# SCH.net
KiCad netlist of a schematic drawn in Altium Designer
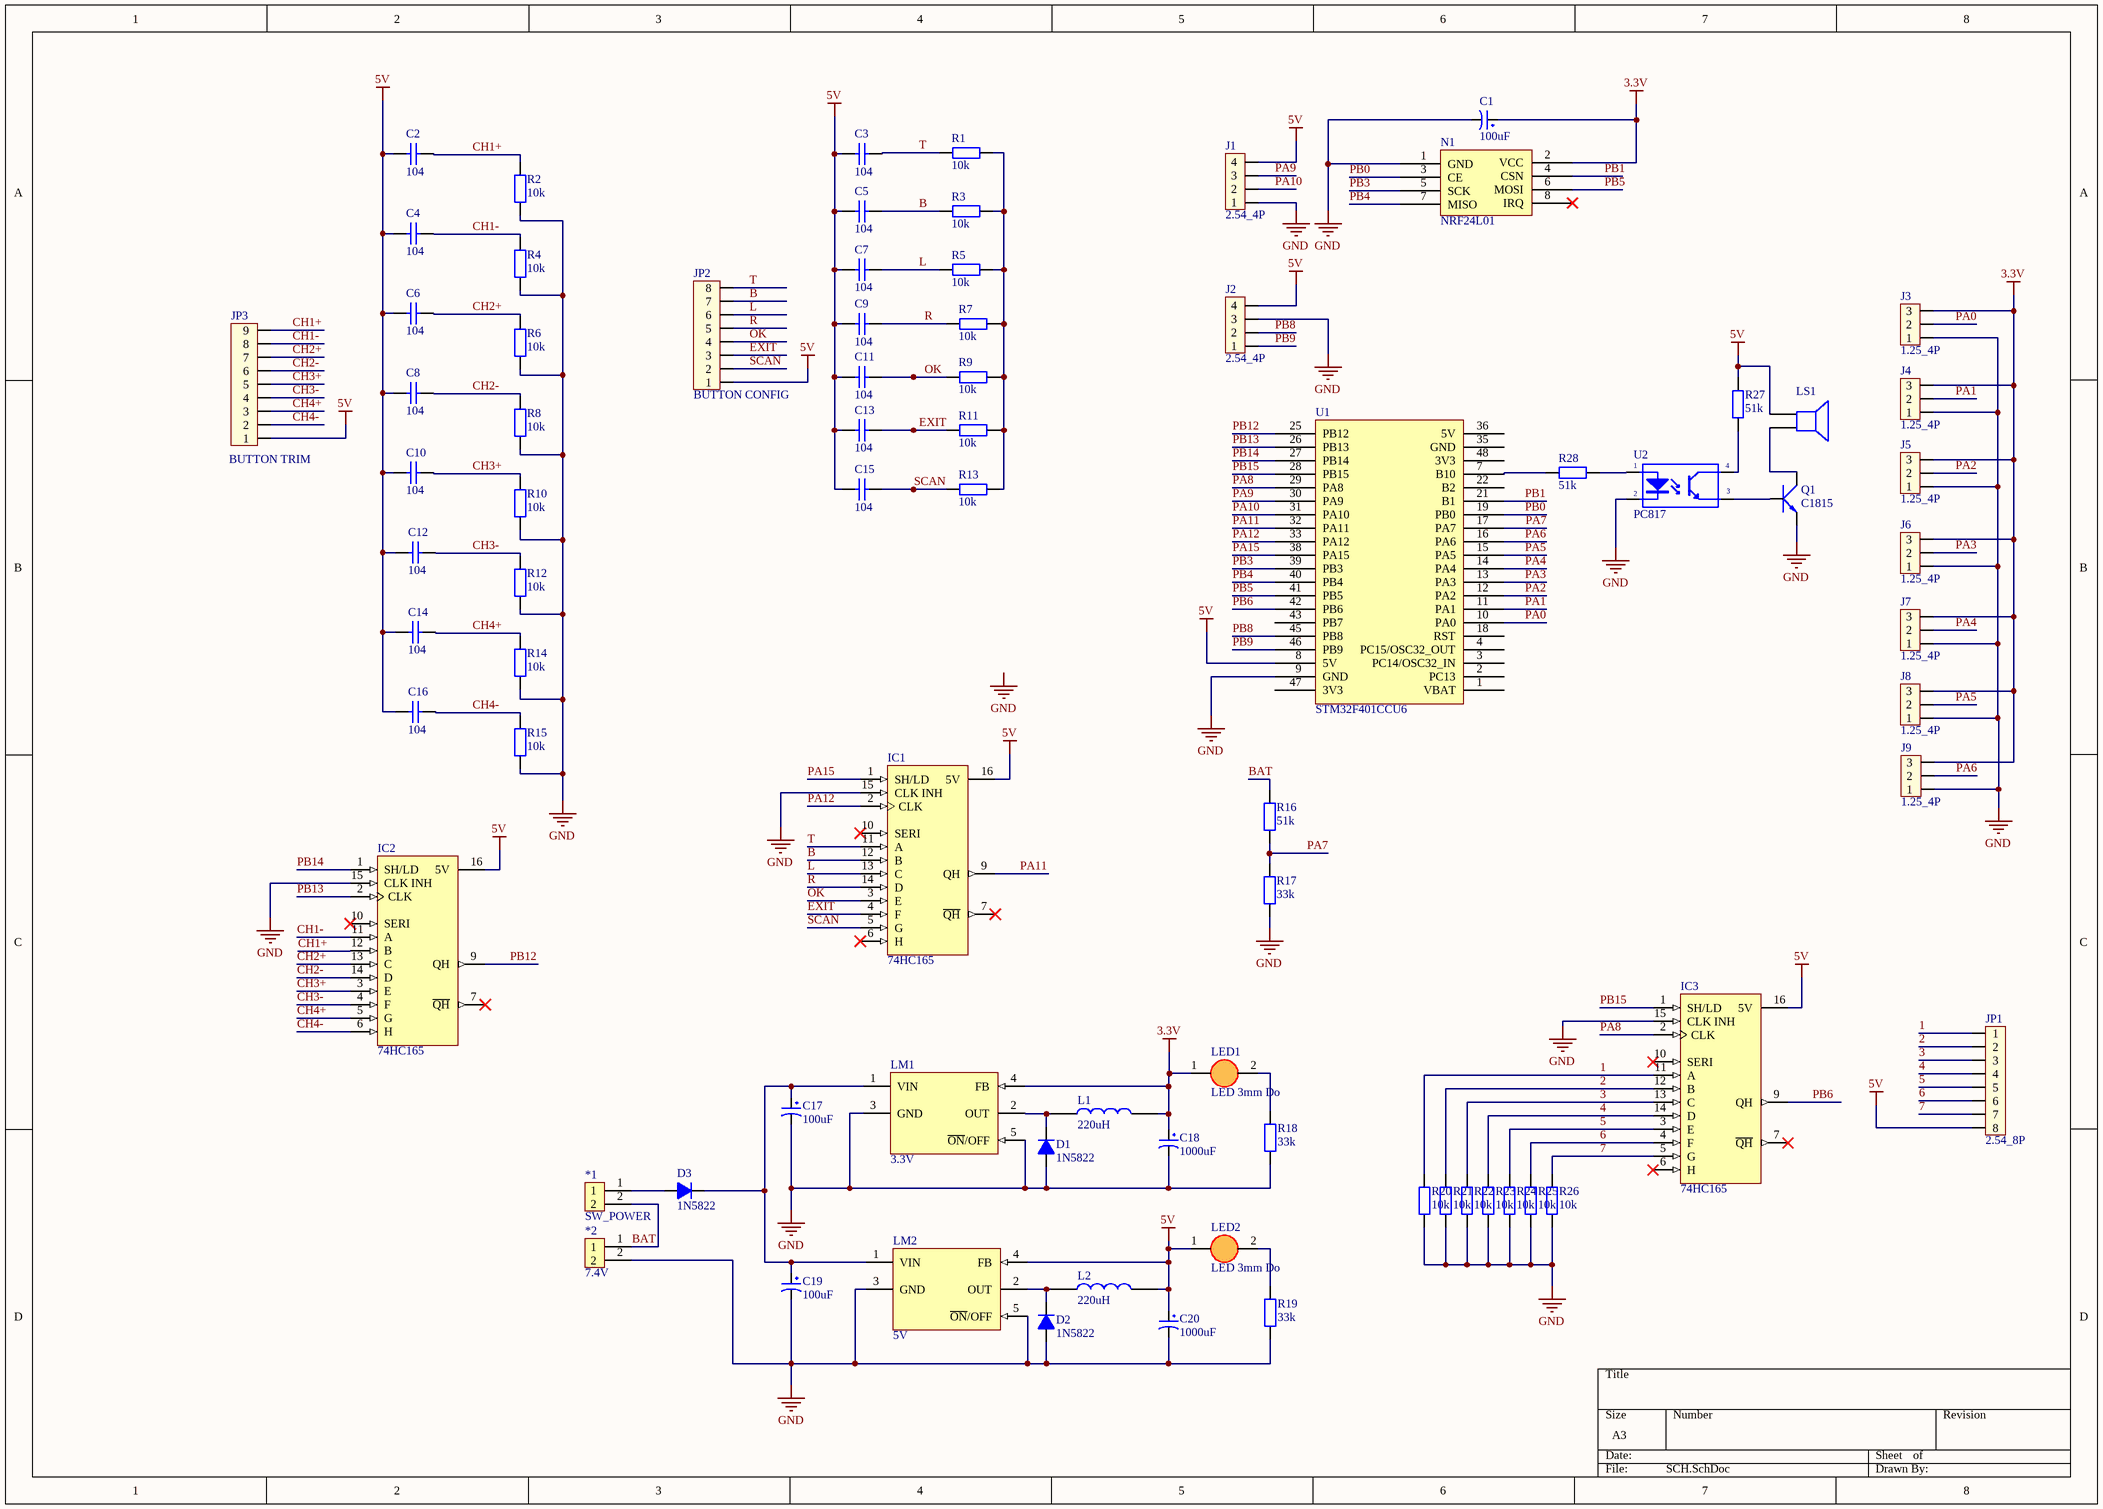
[diagram p0: SCH.SchDoc]

(export (version "E")
  (design (tool "Eeschema 10.0.6"))
  (components
    (comp (ref "*1")
      (value "SW_POWER")
      (footprint "jump don duc_2p")
      (libsource (lib "THU VIEN SCH") (part "jump don duc 2.54_2p"))
    )
    (comp (ref "*2")
      (value "7.4V")
      (footprint "jump don duc_2p")
      (libsource (lib "THU VIEN SCH") (part "jump don duc 2.54_2p"))
    )
    (comp (ref "C1")
      (value "100uF")
      (footprint "tu hoa 5mm")
      (description "Cắm")
      (libsource (lib "THU VIEN SCH") (part "Tu Hoa 100uF 25V 6x11"))
    )
    (comp (ref "C2")
      (value "104")
      (footprint "tu gom")
      (description "Cắm")
      (libsource (lib "THU VIEN SCH") (part "Tu gom 104 50V"))
    )
    (comp (ref "C3")
      (value "104")
      (footprint "tu gom")
      (description "Cắm")
      (libsource (lib "THU VIEN SCH") (part "Tu gom 104 50V"))
    )
    (comp (ref "C4")
      (value "104")
      (footprint "tu gom")
      (description "Cắm")
      (libsource (lib "THU VIEN SCH") (part "Tu gom 104 50V"))
    )
    (comp (ref "C5")
      (value "104")
      (footprint "tu gom")
      (description "Cắm")
      (libsource (lib "THU VIEN SCH") (part "Tu gom 104 50V"))
    )
    (comp (ref "C6")
      (value "104")
      (footprint "tu gom")
      (description "Cắm")
      (libsource (lib "THU VIEN SCH") (part "Tu gom 104 50V"))
    )
    (comp (ref "C7")
      (value "104")
      (footprint "tu gom")
      (description "Cắm")
      (libsource (lib "THU VIEN SCH") (part "Tu gom 104 50V"))
    )
    (comp (ref "C8")
      (value "104")
      (footprint "tu gom")
      (description "Cắm")
      (libsource (lib "THU VIEN SCH") (part "Tu gom 104 50V"))
    )
    (comp (ref "C9")
      (value "104")
      (footprint "tu gom")
      (description "Cắm")
      (libsource (lib "THU VIEN SCH") (part "Tu gom 104 50V"))
    )
    (comp (ref "C10")
      (value "104")
      (footprint "tu gom")
      (description "Cắm")
      (libsource (lib "THU VIEN SCH") (part "Tu gom 104 50V"))
    )
    (comp (ref "C11")
      (value "104")
      (footprint "tu gom")
      (description "Cắm")
      (libsource (lib "THU VIEN SCH") (part "Tu gom 104 50V"))
    )
    (comp (ref "C12")
      (value "104")
      (footprint "tu gom")
      (description "Cắm")
      (libsource (lib "THU VIEN SCH") (part "Tu gom 104 50V"))
    )
    (comp (ref "C13")
      (value "104")
      (footprint "tu gom")
      (description "Cắm")
      (libsource (lib "THU VIEN SCH") (part "Tu gom 104 50V"))
    )
    (comp (ref "C14")
      (value "104")
      (footprint "tu gom")
      (description "Cắm")
      (libsource (lib "THU VIEN SCH") (part "Tu gom 104 50V"))
    )
    (comp (ref "C15")
      (value "104")
      (footprint "tu gom")
      (description "Cắm")
      (libsource (lib "THU VIEN SCH") (part "Tu gom 104 50V"))
    )
    (comp (ref "C16")
      (value "104")
      (footprint "tu gom")
      (description "Cắm")
      (libsource (lib "THU VIEN SCH") (part "Tu gom 104 50V"))
    )
    (comp (ref "C17")
      (value "100uF")
      (footprint "tu hoa 8mm")
      (description "Cắm")
      (libsource (lib "THU VIEN SCH") (part "Tu Hoa 100uF 50V 8x11"))
    )
    (comp (ref "C18")
      (value "1000uF")
      (footprint "tu hoa 8mm")
      (description "Cắm")
      (libsource (lib "THU VIEN SCH") (part "Tu Hoa 1000uF 16V 8x20"))
    )
    (comp (ref "C19")
      (value "100uF")
      (footprint "tu hoa 8mm")
      (description "Cắm")
      (libsource (lib "THU VIEN SCH") (part "Tu Hoa 100uF 50V 8x11"))
    )
    (comp (ref "C20")
      (value "1000uF")
      (footprint "tu hoa 8mm")
      (description "Cắm")
      (libsource (lib "THU VIEN SCH") (part "Tu Hoa 1000uF 16V 8x20"))
    )
    (comp (ref "D1")
      (value "1N5822")
      (footprint "D5A")
      (description "Diode 5A")
      (libsource (lib "syhaunguyen") (part "D5A"))
    )
    (comp (ref "D2")
      (value "1N5822")
      (footprint "D5A")
      (description "Diode 5A")
      (libsource (lib "syhaunguyen") (part "D5A"))
    )
    (comp (ref "D3")
      (value "1N5822")
      (footprint "D5A")
      (description "Diode 5A")
      (libsource (lib "syhaunguyen") (part "D5A"))
    )
    (comp (ref "IC1")
      (value "74HC165")
      (footprint "DIP16/W0.3")
      (description "8-Bit Parallel In/Serial Out Shift Register")
      (libsource (lib "syhaunguyen") (part "74HC165"))
    )
    (comp (ref "IC2")
      (value "74HC165")
      (footprint "DIP16/W0.3")
      (description "8-Bit Parallel In/Serial Out Shift Register")
      (libsource (lib "syhaunguyen") (part "74HC165"))
    )
    (comp (ref "IC3")
      (value "74HC165")
      (footprint "DIP16/W0.3")
      (description "8-Bit Parallel In/Serial Out Shift Register")
      (libsource (lib "syhaunguyen") (part "74HC165"))
    )
    (comp (ref "J1")
      (value "2.54_4P")
      (footprint "JP4")
      (description "Cắm")
      (libsource (lib "THU VIEN SCH") (part "Jum Don Duc 2.54_4P"))
    )
    (comp (ref "J2")
      (value "2.54_4P")
      (footprint "JP4")
      (description "Cắm")
      (libsource (lib "THU VIEN SCH") (part "Jum Don Duc 2.54_4P"))
    )
    (comp (ref "J3")
      (value "1.25_4P")
      (footprint "ZH1.25 3P")
      (description "Cắm")
      (libsource (lib "THU VIEN SCH") (part "ZH1.25 3P"))
    )
    (comp (ref "J4")
      (value "1.25_4P")
      (footprint "ZH1.25 3P")
      (description "Cắm")
      (libsource (lib "THU VIEN SCH") (part "ZH1.25 3P"))
    )
    (comp (ref "J5")
      (value "1.25_4P")
      (footprint "ZH1.25 3P")
      (description "Cắm")
      (libsource (lib "THU VIEN SCH") (part "ZH1.25 3P"))
    )
    (comp (ref "J6")
      (value "1.25_4P")
      (footprint "ZH1.25 3P")
      (description "Cắm")
      (libsource (lib "THU VIEN SCH") (part "ZH1.25 3P"))
    )
    (comp (ref "J7")
      (value "1.25_4P")
      (footprint "ZH1.25 3P")
      (description "Cắm")
      (libsource (lib "THU VIEN SCH") (part "ZH1.25 3P"))
    )
    (comp (ref "J8")
      (value "1.25_4P")
      (footprint "ZH1.25 3P")
      (description "Cắm")
      (libsource (lib "THU VIEN SCH") (part "ZH1.25 3P"))
    )
    (comp (ref "J9")
      (value "1.25_4P")
      (footprint "ZH1.25 3P")
      (description "Cắm")
      (libsource (lib "THU VIEN SCH") (part "ZH1.25 3P"))
    )
    (comp (ref "JP1")
      (value "2.54_8P")
      (footprint "JP8")
      (description "Cắm")
      (libsource (lib "THU VIEN SCH") (part "Jum Don Duc 2.54_8P"))
    )
    (comp (ref "JP2")
      (value "BUTTON CONFIG")
      (footprint "CON8")
      (description "Cắm")
      (libsource (lib "THU VIEN SCH") (part "Con_8"))
    )
    (comp (ref "JP3")
      (value "BUTTON TRIM")
      (footprint "CON9")
      (description "Cắm")
      (libsource (lib "THU VIEN SCH") (part "Con_9"))
    )
    (comp (ref "L1")
      (value "220uH")
      (footprint "CUON CAM 100uH3A")
      (description "Cắm")
      (libsource (lib "THU VIEN SCH") (part "CUON CAM 470uH DIP"))
    )
    (comp (ref "L2")
      (value "220uH")
      (footprint "CUON CAM 100uH3A")
      (description "Cắm")
      (libsource (lib "THU VIEN SCH") (part "CUON CAM 470uH DIP"))
    )
    (comp (ref "LED1")
      (value "LED 3mm Do")
      (footprint "LED 3mm Do")
      (description "Cắm")
      (libsource (lib "THU VIEN SCH") (part "LED 3mm Do"))
    )
    (comp (ref "LED2")
      (value "LED 3mm Do")
      (footprint "LED 3mm Do")
      (description "Cắm")
      (libsource (lib "THU VIEN SCH") (part "LED 3mm Do"))
    )
    (comp (ref "LM1")
      (value "3.3V")
      (footprint "LM2576-5V")
      (description "Cắm")
      (libsource (lib "THU VIEN SCH") (part "LM2576_3.3V."))
    )
    (comp (ref "LM2")
      (value "5V")
      (footprint "LM2576-5V")
      (description "Cắm")
      (libsource (lib "THU VIEN SCH") (part "LM2576_5V"))
    )
    (comp (ref "LS1")
      (value "~")
      (footprint "SPEAKER")
      (description "Cắm")
      (libsource (lib "THU VIEN SCH") (part "Coi Chip 5V"))
    )
    (comp (ref "N1")
      (value "NRF24L01")
      (footprint "NRF24L01")
      (libsource (lib "THU VIEN SCH") (part "NRF24L01"))
    )
    (comp (ref "Q1")
      (value "C1815")
      (footprint "QTO-92")
      (description "NPN 600mW, ECB")
      (libsource (lib "syhaunguyen") (part "C1815"))
    )
    (comp (ref "R1")
      (value "10k")
      (footprint "tro vach 1/4w")
      (description "Căm")
      (libsource (lib "THU VIEN SCH") (part "Tro Vach 1/4W 5% 10k"))
    )
    (comp (ref "R2")
      (value "10k")
      (footprint "tro vach 1/4w")
      (description "Căm")
      (libsource (lib "THU VIEN SCH") (part "Tro Vach 1/4W 5% 10k"))
    )
    (comp (ref "R3")
      (value "10k")
      (footprint "tro vach 1/4w")
      (description "Căm")
      (libsource (lib "THU VIEN SCH") (part "Tro Vach 1/4W 5% 10k"))
    )
    (comp (ref "R4")
      (value "10k")
      (footprint "tro vach 1/4w")
      (description "Căm")
      (libsource (lib "THU VIEN SCH") (part "Tro Vach 1/4W 5% 10k"))
    )
    (comp (ref "R5")
      (value "10k")
      (footprint "tro vach 1/4w")
      (description "Căm")
      (libsource (lib "THU VIEN SCH") (part "Tro Vach 1/4W 5% 10k"))
    )
    (comp (ref "R6")
      (value "10k")
      (footprint "tro vach 1/4w")
      (description "Căm")
      (libsource (lib "THU VIEN SCH") (part "Tro Vach 1/4W 5% 10k"))
    )
    (comp (ref "R7")
      (value "10k")
      (footprint "tro vach 1/4w")
      (description "Căm")
      (libsource (lib "THU VIEN SCH") (part "Tro Vach 1/4W 5% 10k"))
    )
    (comp (ref "R8")
      (value "10k")
      (footprint "tro vach 1/4w")
      (description "Căm")
      (libsource (lib "THU VIEN SCH") (part "Tro Vach 1/4W 5% 10k"))
    )
    (comp (ref "R9")
      (value "10k")
      (footprint "tro vach 1/4w")
      (description "Căm")
      (libsource (lib "THU VIEN SCH") (part "Tro Vach 1/4W 5% 10k"))
    )
    (comp (ref "R10")
      (value "10k")
      (footprint "tro vach 1/4w")
      (description "Căm")
      (libsource (lib "THU VIEN SCH") (part "Tro Vach 1/4W 5% 10k"))
    )
    (comp (ref "R11")
      (value "10k")
      (footprint "tro vach 1/4w")
      (description "Căm")
      (libsource (lib "THU VIEN SCH") (part "Tro Vach 1/4W 5% 10k"))
    )
    (comp (ref "R12")
      (value "10k")
      (footprint "tro vach 1/4w")
      (description "Căm")
      (libsource (lib "THU VIEN SCH") (part "Tro Vach 1/4W 5% 10k"))
    )
    (comp (ref "R13")
      (value "10k")
      (footprint "tro vach 1/4w")
      (description "Căm")
      (libsource (lib "THU VIEN SCH") (part "Tro Vach 1/4W 5% 10k"))
    )
    (comp (ref "R14")
      (value "10k")
      (footprint "tro vach 1/4w")
      (description "Căm")
      (libsource (lib "THU VIEN SCH") (part "Tro Vach 1/4W 5% 10k"))
    )
    (comp (ref "R15")
      (value "10k")
      (footprint "tro vach 1/4w")
      (description "Căm")
      (libsource (lib "THU VIEN SCH") (part "Tro Vach 1/4W 5% 10k"))
    )
    (comp (ref "R16")
      (value "51k")
      (footprint "tro vach 1/4w")
      (description "Căm")
      (libsource (lib "THU VIEN SCH") (part "Tro Vach 1/4W 5% 10k"))
    )
    (comp (ref "R17")
      (value "33k")
      (footprint "tro vach 1/4w")
      (description "Căm")
      (libsource (lib "THU VIEN SCH") (part "Tro Vach 1/4W 5% 10k"))
    )
    (comp (ref "R18")
      (value "33k")
      (footprint "tro vach 1/4w")
      (description "Căm")
      (libsource (lib "THU VIEN SCH") (part "Tro Vach 1/4W 5% 10k"))
    )
    (comp (ref "R19")
      (value "33k")
      (footprint "tro vach 1/4w")
      (description "Căm")
      (libsource (lib "THU VIEN SCH") (part "Tro Vach 1/4W 5% 10k"))
    )
    (comp (ref "R20")
      (value "10k")
      (footprint "tro vach 1/4w")
      (description "Căm")
      (libsource (lib "THU VIEN SCH") (part "Tro Vach 1/4W 5% 10k"))
    )
    (comp (ref "R21")
      (value "10k")
      (footprint "tro vach 1/4w")
      (description "Căm")
      (libsource (lib "THU VIEN SCH") (part "Tro Vach 1/4W 5% 10k"))
    )
    (comp (ref "R22")
      (value "10k")
      (footprint "tro vach 1/4w")
      (description "Căm")
      (libsource (lib "THU VIEN SCH") (part "Tro Vach 1/4W 5% 10k"))
    )
    (comp (ref "R23")
      (value "10k")
      (footprint "tro vach 1/4w")
      (description "Căm")
      (libsource (lib "THU VIEN SCH") (part "Tro Vach 1/4W 5% 10k"))
    )
    (comp (ref "R24")
      (value "10k")
      (footprint "tro vach 1/4w")
      (description "Căm")
      (libsource (lib "THU VIEN SCH") (part "Tro Vach 1/4W 5% 10k"))
    )
    (comp (ref "R25")
      (value "10k")
      (footprint "tro vach 1/4w")
      (description "Căm")
      (libsource (lib "THU VIEN SCH") (part "Tro Vach 1/4W 5% 10k"))
    )
    (comp (ref "R26")
      (value "10k")
      (footprint "tro vach 1/4w")
      (description "Căm")
      (libsource (lib "THU VIEN SCH") (part "Tro Vach 1/4W 5% 10k"))
    )
    (comp (ref "R27")
      (value "51k")
      (footprint "tro vach 1/4w")
      (description "Căm")
      (libsource (lib "THU VIEN SCH") (part "Tro Vach 1/4W 5% 10k"))
    )
    (comp (ref "R28")
      (value "51k")
      (footprint "tro vach 1/4w")
      (description "Căm")
      (libsource (lib "THU VIEN SCH") (part "Tro Vach 1/4W 5% 10k"))
    )
    (comp (ref "U1")
      (value "STM32F401CCU6")
      (footprint "STM32F401CCU6")
      (libsource (lib "THU VIEN SCH") (part "STM32F401CCU6"))
    )
    (comp (ref "U2")
      (value "PC817")
      (footprint "DIP4/W0.3")
      (description "Single Opto")
      (libsource (lib "syhaunguyen") (part "PC817"))
    )
  )
  (nets
    (net (code "1") (name "/1") (class "Default")
      (node (ref "IC3") (pin "11") (pinfunction "A_11") (pintype "input"))
      (node (ref "JP1") (pin "1") (pinfunction "1_1") (pintype "passive"))
      (node (ref "R20") (pin "2") (pinfunction "2_2") (pintype "passive"))
    )
    (net (code "2") (name "/2") (class "Default")
      (node (ref "IC3") (pin "12") (pinfunction "B_12") (pintype "input"))
      (node (ref "JP1") (pin "2") (pinfunction "2_2") (pintype "passive"))
      (node (ref "R21") (pin "2") (pinfunction "2_2") (pintype "passive"))
    )
    (net (code "3") (name "/3") (class "Default")
      (node (ref "IC3") (pin "13") (pinfunction "C_13") (pintype "input"))
      (node (ref "JP1") (pin "3") (pinfunction "3_3") (pintype "passive"))
      (node (ref "R22") (pin "2") (pinfunction "2_2") (pintype "passive"))
    )
    (net (code "4") (name "/4") (class "Default")
      (node (ref "IC3") (pin "14") (pinfunction "D_14") (pintype "input"))
      (node (ref "JP1") (pin "4") (pinfunction "4_4") (pintype "passive"))
      (node (ref "R23") (pin "2") (pinfunction "2_2") (pintype "passive"))
    )
    (net (code "5") (name "/5") (class "Default")
      (node (ref "IC3") (pin "3") (pinfunction "E_3") (pintype "input"))
      (node (ref "JP1") (pin "5") (pinfunction "5_5") (pintype "passive"))
      (node (ref "R24") (pin "2") (pinfunction "2_2") (pintype "passive"))
    )
    (net (code "6") (name "/6") (class "Default")
      (node (ref "IC3") (pin "4") (pinfunction "F_4") (pintype "input"))
      (node (ref "JP1") (pin "6") (pinfunction "6_6") (pintype "passive"))
      (node (ref "R25") (pin "2") (pinfunction "2_2") (pintype "passive"))
    )
    (net (code "7") (name "/7") (class "Default")
      (node (ref "IC3") (pin "5") (pinfunction "G_5") (pintype "input"))
      (node (ref "JP1") (pin "7") (pinfunction "7_7") (pintype "passive"))
      (node (ref "R26") (pin "2") (pinfunction "2_2") (pintype "passive"))
    )
    (net (code "8") (name "/B") (class "Default")
      (node (ref "C5") (pin "1") (pinfunction "1_1") (pintype "passive"))
      (node (ref "IC1") (pin "12") (pinfunction "B_12") (pintype "input"))
      (node (ref "JP2") (pin "7") (pinfunction "7_7") (pintype "passive"))
      (node (ref "R3") (pin "1") (pinfunction "1_1") (pintype "passive"))
    )
    (net (code "9") (name "/BAT") (class "Default")
      (node (ref "*1") (pin "2") (pinfunction "2_2") (pintype "passive"))
      (node (ref "*2") (pin "1") (pinfunction "1_1") (pintype "passive"))
      (node (ref "R16") (pin "2") (pinfunction "2_2") (pintype "passive"))
    )
    (net (code "10") (name "/CH1+") (class "Default")
      (node (ref "C2") (pin "1") (pinfunction "1_1") (pintype "passive"))
      (node (ref "IC2") (pin "12") (pinfunction "B_12") (pintype "input"))
      (node (ref "JP3") (pin "9") (pinfunction "9_9") (pintype "passive"))
      (node (ref "R2") (pin "1") (pinfunction "1_1") (pintype "passive"))
    )
    (net (code "11") (name "/CH1-") (class "Default")
      (node (ref "C4") (pin "1") (pinfunction "1_1") (pintype "passive"))
      (node (ref "IC2") (pin "11") (pinfunction "A_11") (pintype "input"))
      (node (ref "JP3") (pin "8") (pinfunction "8_8") (pintype "passive"))
      (node (ref "R4") (pin "2") (pinfunction "2_2") (pintype "passive"))
    )
    (net (code "12") (name "/CH2+") (class "Default")
      (node (ref "C6") (pin "1") (pinfunction "1_1") (pintype "passive"))
      (node (ref "IC2") (pin "13") (pinfunction "C_13") (pintype "input"))
      (node (ref "JP3") (pin "7") (pinfunction "7_7") (pintype "passive"))
      (node (ref "R6") (pin "2") (pinfunction "2_2") (pintype "passive"))
    )
    (net (code "13") (name "/CH2-") (class "Default")
      (node (ref "C8") (pin "1") (pinfunction "1_1") (pintype "passive"))
      (node (ref "IC2") (pin "14") (pinfunction "D_14") (pintype "input"))
      (node (ref "JP3") (pin "6") (pinfunction "6_6") (pintype "passive"))
      (node (ref "R8") (pin "2") (pinfunction "2_2") (pintype "passive"))
    )
    (net (code "14") (name "/CH3+") (class "Default")
      (node (ref "C10") (pin "1") (pinfunction "1_1") (pintype "passive"))
      (node (ref "IC2") (pin "3") (pinfunction "E_3") (pintype "input"))
      (node (ref "JP3") (pin "5") (pinfunction "5_5") (pintype "passive"))
      (node (ref "R10") (pin "2") (pinfunction "2_2") (pintype "passive"))
    )
    (net (code "15") (name "/CH3-") (class "Default")
      (node (ref "C12") (pin "1") (pinfunction "1_1") (pintype "passive"))
      (node (ref "IC2") (pin "4") (pinfunction "F_4") (pintype "input"))
      (node (ref "JP3") (pin "4") (pinfunction "4_4") (pintype "passive"))
      (node (ref "R12") (pin "2") (pinfunction "2_2") (pintype "passive"))
    )
    (net (code "16") (name "/CH4+") (class "Default")
      (node (ref "C14") (pin "1") (pinfunction "1_1") (pintype "passive"))
      (node (ref "IC2") (pin "5") (pinfunction "G_5") (pintype "input"))
      (node (ref "JP3") (pin "3") (pinfunction "3_3") (pintype "passive"))
      (node (ref "R14") (pin "2") (pinfunction "2_2") (pintype "passive"))
    )
    (net (code "17") (name "/CH4-") (class "Default")
      (node (ref "C16") (pin "1") (pinfunction "1_1") (pintype "passive"))
      (node (ref "IC2") (pin "6") (pinfunction "H_6") (pintype "input"))
      (node (ref "JP3") (pin "2") (pinfunction "2_2") (pintype "passive"))
      (node (ref "R15") (pin "2") (pinfunction "2_2") (pintype "passive"))
    )
    (net (code "18") (name "/EXIT") (class "Default")
      (node (ref "C13") (pin "1") (pinfunction "1_1") (pintype "passive"))
      (node (ref "IC1") (pin "4") (pinfunction "F_4") (pintype "input"))
      (node (ref "JP2") (pin "3") (pinfunction "3_3") (pintype "passive"))
      (node (ref "R11") (pin "1") (pinfunction "1_1") (pintype "passive"))
    )
    (net (code "19") (name "/L") (class "Default")
      (node (ref "C7") (pin "1") (pinfunction "1_1") (pintype "passive"))
      (node (ref "IC1") (pin "13") (pinfunction "C_13") (pintype "input"))
      (node (ref "JP2") (pin "6") (pinfunction "6_6") (pintype "passive"))
      (node (ref "R5") (pin "1") (pinfunction "1_1") (pintype "passive"))
    )
    (net (code "20") (name "/OK") (class "Default")
      (node (ref "C11") (pin "1") (pinfunction "1_1") (pintype "passive"))
      (node (ref "IC1") (pin "3") (pinfunction "E_3") (pintype "input"))
      (node (ref "JP2") (pin "4") (pinfunction "4_4") (pintype "passive"))
      (node (ref "R9") (pin "1") (pinfunction "1_1") (pintype "passive"))
    )
    (net (code "21") (name "/PA0") (class "Default")
      (node (ref "J3") (pin "2") (pinfunction "2_2") (pintype "passive"))
      (node (ref "U1") (pin "10") (pinfunction "PA0_10") (pintype "passive"))
    )
    (net (code "22") (name "/PA1") (class "Default")
      (node (ref "J4") (pin "2") (pinfunction "2_2") (pintype "passive"))
      (node (ref "U1") (pin "11") (pinfunction "PA1_11") (pintype "passive"))
    )
    (net (code "23") (name "/PA2") (class "Default")
      (node (ref "J5") (pin "2") (pinfunction "2_2") (pintype "passive"))
      (node (ref "U1") (pin "12") (pinfunction "PA2_12") (pintype "passive"))
    )
    (net (code "24") (name "/PA3") (class "Default")
      (node (ref "J6") (pin "2") (pinfunction "2_2") (pintype "passive"))
      (node (ref "U1") (pin "13") (pinfunction "PA3_13") (pintype "passive"))
    )
    (net (code "25") (name "/PA4") (class "Default")
      (node (ref "J7") (pin "2") (pinfunction "2_2") (pintype "passive"))
      (node (ref "U1") (pin "14") (pinfunction "PA4_14") (pintype "passive"))
    )
    (net (code "26") (name "/PA5") (class "Default")
      (node (ref "J8") (pin "2") (pinfunction "2_2") (pintype "passive"))
      (node (ref "U1") (pin "15") (pinfunction "PA5_15") (pintype "passive"))
    )
    (net (code "27") (name "/PA6") (class "Default")
      (node (ref "J9") (pin "2") (pinfunction "2_2") (pintype "passive"))
      (node (ref "U1") (pin "16") (pinfunction "PA6_16") (pintype "passive"))
    )
    (net (code "28") (name "/PA7") (class "Default")
      (node (ref "R16") (pin "1") (pinfunction "1_1") (pintype "passive"))
      (node (ref "R17") (pin "2") (pinfunction "2_2") (pintype "passive"))
      (node (ref "U1") (pin "17") (pinfunction "PA7_17") (pintype "passive"))
    )
    (net (code "29") (name "/PA8") (class "Default")
      (node (ref "IC3") (pin "2") (pinfunction "CLK_2") (pintype "input"))
      (node (ref "U1") (pin "29") (pinfunction "PA8_29") (pintype "passive"))
    )
    (net (code "30") (name "/PA9") (class "Default")
      (node (ref "J1") (pin "3") (pinfunction "3_3") (pintype "passive"))
      (node (ref "U1") (pin "30") (pinfunction "PA9_30") (pintype "passive"))
    )
    (net (code "31") (name "/PA10") (class "Default")
      (node (ref "J1") (pin "2") (pinfunction "2_2") (pintype "passive"))
      (node (ref "U1") (pin "31") (pinfunction "PA10_31") (pintype "passive"))
    )
    (net (code "32") (name "/PA11") (class "Default")
      (node (ref "IC1") (pin "9") (pinfunction "QH_9") (pintype "output"))
      (node (ref "U1") (pin "32") (pinfunction "PA11_32") (pintype "passive"))
    )
    (net (code "33") (name "/PA12") (class "Default")
      (node (ref "IC1") (pin "2") (pinfunction "CLK_2") (pintype "input"))
      (node (ref "U1") (pin "33") (pinfunction "PA12_33") (pintype "passive"))
    )
    (net (code "34") (name "/PA15") (class "Default")
      (node (ref "IC1") (pin "1") (pinfunction "SH/LD_1") (pintype "input"))
      (node (ref "U1") (pin "38") (pinfunction "PA15_38") (pintype "passive"))
    )
    (net (code "35") (name "/PB0") (class "Default")
      (node (ref "N1") (pin "3") (pinfunction "CE_3") (pintype "passive"))
      (node (ref "U1") (pin "19") (pinfunction "PB0_19") (pintype "passive"))
    )
    (net (code "36") (name "/PB1") (class "Default")
      (node (ref "N1") (pin "4") (pinfunction "CSN_4") (pintype "passive"))
      (node (ref "U1") (pin "21") (pinfunction "B1_21") (pintype "passive"))
    )
    (net (code "37") (name "/PB3") (class "Default")
      (node (ref "N1") (pin "5") (pinfunction "SCK_5") (pintype "passive"))
      (node (ref "U1") (pin "39") (pinfunction "PB3_39") (pintype "passive"))
    )
    (net (code "38") (name "/PB4") (class "Default")
      (node (ref "N1") (pin "7") (pinfunction "MISO_7") (pintype "passive"))
      (node (ref "U1") (pin "40") (pinfunction "PB4_40") (pintype "passive"))
    )
    (net (code "39") (name "/PB5") (class "Default")
      (node (ref "N1") (pin "6") (pinfunction "MOSI_6") (pintype "passive"))
      (node (ref "U1") (pin "41") (pinfunction "PB5_41") (pintype "passive"))
    )
    (net (code "40") (name "/PB6") (class "Default")
      (node (ref "IC3") (pin "9") (pinfunction "QH_9") (pintype "output"))
      (node (ref "U1") (pin "42") (pinfunction "PB6_42") (pintype "passive"))
    )
    (net (code "41") (name "/PB8") (class "Default")
      (node (ref "J2") (pin "2") (pinfunction "2_2") (pintype "passive"))
      (node (ref "U1") (pin "45") (pinfunction "PB8_45") (pintype "passive"))
    )
    (net (code "42") (name "/PB9") (class "Default")
      (node (ref "J2") (pin "1") (pinfunction "1_1") (pintype "passive"))
      (node (ref "U1") (pin "46") (pinfunction "PB9_46") (pintype "passive"))
    )
    (net (code "43") (name "/PB12") (class "Default")
      (node (ref "IC2") (pin "9") (pinfunction "QH_9") (pintype "output"))
      (node (ref "U1") (pin "25") (pinfunction "PB12_25") (pintype "passive"))
    )
    (net (code "44") (name "/PB13") (class "Default")
      (node (ref "IC2") (pin "2") (pinfunction "CLK_2") (pintype "input"))
      (node (ref "U1") (pin "26") (pinfunction "PB13_26") (pintype "passive"))
    )
    (net (code "45") (name "/PB14") (class "Default")
      (node (ref "IC2") (pin "1") (pinfunction "SH/LD_1") (pintype "input"))
      (node (ref "U1") (pin "27") (pinfunction "PB14_27") (pintype "passive"))
    )
    (net (code "46") (name "/PB15") (class "Default")
      (node (ref "IC3") (pin "1") (pinfunction "SH/LD_1") (pintype "input"))
      (node (ref "U1") (pin "28") (pinfunction "PB15_28") (pintype "passive"))
    )
    (net (code "47") (name "/R") (class "Default")
      (node (ref "C9") (pin "1") (pinfunction "1_1") (pintype "passive"))
      (node (ref "IC1") (pin "14") (pinfunction "D_14") (pintype "input"))
      (node (ref "JP2") (pin "5") (pinfunction "5_5") (pintype "passive"))
      (node (ref "R7") (pin "1") (pinfunction "1_1") (pintype "passive"))
    )
    (net (code "48") (name "/SCAN") (class "Default")
      (node (ref "C15") (pin "1") (pinfunction "1_1") (pintype "passive"))
      (node (ref "IC1") (pin "5") (pinfunction "G_5") (pintype "input"))
      (node (ref "JP2") (pin "2") (pinfunction "2_2") (pintype "passive"))
      (node (ref "R13") (pin "1") (pinfunction "1_1") (pintype "passive"))
    )
    (net (code "49") (name "/T") (class "Default")
      (node (ref "C3") (pin "1") (pinfunction "1_1") (pintype "passive"))
      (node (ref "IC1") (pin "11") (pinfunction "A_11") (pintype "input"))
      (node (ref "JP2") (pin "8") (pinfunction "8_8") (pintype "passive"))
      (node (ref "R1") (pin "1") (pinfunction "1_1") (pintype "passive"))
    )
    (net (code "50") (name "3.3V") (class "Default")
      (node (ref "C1") (pin "1") (pinfunction "1_1") (pintype "passive"))
      (node (ref "C18") (pin "1") (pinfunction "1_1") (pintype "passive"))
      (node (ref "J3") (pin "3") (pinfunction "3_3") (pintype "passive"))
      (node (ref "J4") (pin "3") (pinfunction "3_3") (pintype "passive"))
      (node (ref "J5") (pin "3") (pinfunction "3_3") (pintype "passive"))
      (node (ref "J6") (pin "3") (pinfunction "3_3") (pintype "passive"))
      (node (ref "J7") (pin "3") (pinfunction "3_3") (pintype "passive"))
      (node (ref "J8") (pin "3") (pinfunction "3_3") (pintype "passive"))
      (node (ref "J9") (pin "3") (pinfunction "3_3") (pintype "passive"))
      (node (ref "L1") (pin "2") (pinfunction "2_2") (pintype "passive"))
      (node (ref "LED1") (pin "1") (pinfunction "A_1") (pintype "passive"))
      (node (ref "LM1") (pin "4") (pinfunction "FB_4") (pintype "input"))
      (node (ref "N1") (pin "2") (pinfunction "VCC_2") (pintype "passive"))
    )
    (net (code "51") (name "5V") (class "Default")
      (node (ref "C10") (pin "2") (pinfunction "2_2") (pintype "passive"))
      (node (ref "C11") (pin "2") (pinfunction "2_2") (pintype "passive"))
      (node (ref "C12") (pin "2") (pinfunction "2_2") (pintype "passive"))
      (node (ref "C13") (pin "2") (pinfunction "2_2") (pintype "passive"))
      (node (ref "C14") (pin "2") (pinfunction "2_2") (pintype "passive"))
      (node (ref "C15") (pin "2") (pinfunction "2_2") (pintype "passive"))
      (node (ref "C16") (pin "2") (pinfunction "2_2") (pintype "passive"))
      (node (ref "C2") (pin "2") (pinfunction "2_2") (pintype "passive"))
      (node (ref "C20") (pin "1") (pinfunction "1_1") (pintype "passive"))
      (node (ref "C3") (pin "2") (pinfunction "2_2") (pintype "passive"))
      (node (ref "C4") (pin "2") (pinfunction "2_2") (pintype "passive"))
      (node (ref "C5") (pin "2") (pinfunction "2_2") (pintype "passive"))
      (node (ref "C6") (pin "2") (pinfunction "2_2") (pintype "passive"))
      (node (ref "C7") (pin "2") (pinfunction "2_2") (pintype "passive"))
      (node (ref "C8") (pin "2") (pinfunction "2_2") (pintype "passive"))
      (node (ref "C9") (pin "2") (pinfunction "2_2") (pintype "passive"))
      (node (ref "IC1") (pin "16") (pinfunction "5V_16") (pintype "power_in"))
      (node (ref "IC2") (pin "16") (pinfunction "5V_16") (pintype "power_in"))
      (node (ref "IC3") (pin "16") (pinfunction "5V_16") (pintype "power_in"))
      (node (ref "J1") (pin "4") (pinfunction "4_4") (pintype "passive"))
      (node (ref "J2") (pin "4") (pinfunction "4_4") (pintype "passive"))
      (node (ref "JP1") (pin "8") (pinfunction "8_8") (pintype "passive"))
      (node (ref "JP2") (pin "1") (pinfunction "1_1") (pintype "passive"))
      (node (ref "JP3") (pin "1") (pinfunction "1_1") (pintype "passive"))
      (node (ref "L2") (pin "2") (pinfunction "2_2") (pintype "passive"))
      (node (ref "LED2") (pin "1") (pinfunction "A_1") (pintype "passive"))
      (node (ref "LM2") (pin "4") (pinfunction "FB_4") (pintype "input"))
      (node (ref "LS1") (pin "1") (pinfunction "1_1") (pintype "passive"))
      (node (ref "R27") (pin "2") (pinfunction "2_2") (pintype "passive"))
      (node (ref "U1") (pin "8") (pinfunction "5V_8") (pintype "passive"))
    )
    (net (code "52") (name "GND") (class "Default")
      (node (ref "*2") (pin "2") (pinfunction "2_2") (pintype "passive"))
      (node (ref "C1") (pin "2") (pinfunction "2_2") (pintype "passive"))
      (node (ref "C17") (pin "2") (pinfunction "2_2") (pintype "passive"))
      (node (ref "C18") (pin "2") (pinfunction "2_2") (pintype "passive"))
      (node (ref "C19") (pin "2") (pinfunction "2_2") (pintype "passive"))
      (node (ref "C20") (pin "2") (pinfunction "2_2") (pintype "passive"))
      (node (ref "D1") (pin "1") (pinfunction "A_1") (pintype "passive"))
      (node (ref "D2") (pin "1") (pinfunction "A_1") (pintype "passive"))
      (node (ref "IC1") (pin "15") (pinfunction "CLK_INH_15") (pintype "input"))
      (node (ref "IC1") (pin "8") (pinfunction "GND_8") (pintype "power_in"))
      (node (ref "IC2") (pin "15") (pinfunction "CLK_INH_15") (pintype "input"))
      (node (ref "IC2") (pin "8") (pinfunction "GND_8") (pintype "power_in"))
      (node (ref "IC3") (pin "15") (pinfunction "CLK_INH_15") (pintype "input"))
      (node (ref "IC3") (pin "8") (pinfunction "GND_8") (pintype "power_in"))
      (node (ref "J1") (pin "1") (pinfunction "1_1") (pintype "passive"))
      (node (ref "J2") (pin "3") (pinfunction "3_3") (pintype "passive"))
      (node (ref "J3") (pin "1") (pinfunction "1_1") (pintype "passive"))
      (node (ref "J4") (pin "1") (pinfunction "1_1") (pintype "passive"))
      (node (ref "J5") (pin "1") (pinfunction "1_1") (pintype "passive"))
      (node (ref "J6") (pin "1") (pinfunction "1_1") (pintype "passive"))
      (node (ref "J7") (pin "1") (pinfunction "1_1") (pintype "passive"))
      (node (ref "J8") (pin "1") (pinfunction "1_1") (pintype "passive"))
      (node (ref "J9") (pin "1") (pinfunction "1_1") (pintype "passive"))
      (node (ref "LM1") (pin "3") (pinfunction "GND_3") (pintype "power_in"))
      (node (ref "LM1") (pin "5") (pinfunction "~{ON}/OFF_5") (pintype "input"))
      (node (ref "LM2") (pin "3") (pinfunction "GND_3") (pintype "power_in"))
      (node (ref "LM2") (pin "5") (pinfunction "~{ON}/OFF_5") (pintype "input"))
      (node (ref "N1") (pin "1") (pinfunction "GND_1") (pintype "passive"))
      (node (ref "Q1") (pin "3") (pinfunction "E_3") (pintype "passive"))
      (node (ref "R10") (pin "1") (pinfunction "1_1") (pintype "passive"))
      (node (ref "R12") (pin "1") (pinfunction "1_1") (pintype "passive"))
      (node (ref "R14") (pin "1") (pinfunction "1_1") (pintype "passive"))
      (node (ref "R15") (pin "1") (pinfunction "1_1") (pintype "passive"))
      (node (ref "R17") (pin "1") (pinfunction "1_1") (pintype "passive"))
      (node (ref "R18") (pin "2") (pinfunction "2_2") (pintype "passive"))
      (node (ref "R19") (pin "2") (pinfunction "2_2") (pintype "passive"))
      (node (ref "R2") (pin "2") (pinfunction "2_2") (pintype "passive"))
      (node (ref "R20") (pin "1") (pinfunction "1_1") (pintype "passive"))
      (node (ref "R21") (pin "1") (pinfunction "1_1") (pintype "passive"))
      (node (ref "R22") (pin "1") (pinfunction "1_1") (pintype "passive"))
      (node (ref "R23") (pin "1") (pinfunction "1_1") (pintype "passive"))
      (node (ref "R24") (pin "1") (pinfunction "1_1") (pintype "passive"))
      (node (ref "R25") (pin "1") (pinfunction "1_1") (pintype "passive"))
      (node (ref "R26") (pin "1") (pinfunction "1_1") (pintype "passive"))
      (node (ref "R4") (pin "1") (pinfunction "1_1") (pintype "passive"))
      (node (ref "R6") (pin "1") (pinfunction "1_1") (pintype "passive"))
      (node (ref "R8") (pin "1") (pinfunction "1_1") (pintype "passive"))
      (node (ref "U1") (pin "9") (pinfunction "GND_9") (pintype "passive"))
      (node (ref "U2") (pin "2") (pinfunction "K_2") (pintype "passive"))
    )
    (net (code "53") (name "Net-(D1-K)") (class "Default")
      (node (ref "D1") (pin "2") (pinfunction "K_2") (pintype "passive"))
      (node (ref "L1") (pin "1") (pinfunction "1_1") (pintype "passive"))
      (node (ref "LM1") (pin "2") (pinfunction "OUT_2") (pintype "power_in"))
    )
    (net (code "54") (name "Net-(D2-K)") (class "Default")
      (node (ref "D2") (pin "2") (pinfunction "K_2") (pintype "passive"))
      (node (ref "L2") (pin "1") (pinfunction "1_1") (pintype "passive"))
      (node (ref "LM2") (pin "2") (pinfunction "OUT_2") (pintype "power_in"))
    )
    (net (code "55") (name "Net-(D3-A)") (class "Default")
      (node (ref "*1") (pin "1") (pinfunction "1_1") (pintype "passive"))
      (node (ref "D3") (pin "1") (pinfunction "A_1") (pintype "passive"))
    )
    (net (code "56") (name "Net-(D3-K)") (class "Default")
      (node (ref "C17") (pin "1") (pinfunction "1_1") (pintype "passive"))
      (node (ref "C19") (pin "1") (pinfunction "1_1") (pintype "passive"))
      (node (ref "D3") (pin "2") (pinfunction "K_2") (pintype "passive"))
      (node (ref "LM1") (pin "1") (pinfunction "VIN_1") (pintype "power_in"))
      (node (ref "LM2") (pin "1") (pinfunction "VIN_1") (pintype "power_in"))
    )
    (net (code "57") (name "Net-(LED1-K)") (class "Default")
      (node (ref "LED1") (pin "2") (pinfunction "K_2") (pintype "passive"))
      (node (ref "R18") (pin "1") (pinfunction "1_1") (pintype "passive"))
    )
    (net (code "58") (name "Net-(LED2-K)") (class "Default")
      (node (ref "LED2") (pin "2") (pinfunction "K_2") (pintype "passive"))
      (node (ref "R19") (pin "1") (pinfunction "1_1") (pintype "passive"))
    )
    (net (code "59") (name "Net-(Q1-B)") (class "Default")
      (node (ref "Q1") (pin "2") (pinfunction "B_2") (pintype "passive"))
      (node (ref "U2") (pin "3") (pinfunction "E_3") (pintype "passive"))
    )
    (net (code "60") (name "Net-(Q1-C)") (class "Default")
      (node (ref "LS1") (pin "2") (pinfunction "2_2") (pintype "passive"))
      (node (ref "Q1") (pin "1") (pinfunction "C_1") (pintype "passive"))
    )
    (net (code "61") (name "Net-(R1-Pad2)") (class "Default")
      (node (ref "R1") (pin "2") (pinfunction "2_2") (pintype "passive"))
      (node (ref "R11") (pin "2") (pinfunction "2_2") (pintype "passive"))
      (node (ref "R13") (pin "2") (pinfunction "2_2") (pintype "passive"))
      (node (ref "R3") (pin "2") (pinfunction "2_2") (pintype "passive"))
      (node (ref "R5") (pin "2") (pinfunction "2_2") (pintype "passive"))
      (node (ref "R7") (pin "2") (pinfunction "2_2") (pintype "passive"))
      (node (ref "R9") (pin "2") (pinfunction "2_2") (pintype "passive"))
    )
    (net (code "62") (name "Net-(U1-B10)") (class "Default")
      (node (ref "R28") (pin "2") (pinfunction "2_2") (pintype "passive"))
      (node (ref "U1") (pin "7") (pinfunction "B10_7") (pintype "passive"))
    )
    (net (code "63") (name "Net-(U2-A)") (class "Default")
      (node (ref "R28") (pin "1") (pinfunction "1_1") (pintype "passive"))
      (node (ref "U2") (pin "1") (pinfunction "A_1") (pintype "passive"))
    )
    (net (code "64") (name "Net-(U2-C)") (class "Default")
      (node (ref "R27") (pin "1") (pinfunction "1_1") (pintype "passive"))
      (node (ref "U2") (pin "4") (pinfunction "C_4") (pintype "passive"))
    )
    (net (code "65") (name "unconnected-(IC1-H-Pad6)") (class "Default")
      (node (ref "IC1") (pin "6") (pinfunction "H_6") (pintype "input+no_connect"))
    )
    (net (code "66") (name "unconnected-(IC1-SERI-Pad10)") (class "Default")
      (node (ref "IC1") (pin "10") (pinfunction "SERI_10") (pintype "input+no_connect"))
    )
    (net (code "67") (name "unconnected-(IC1-~{QH}-Pad7)") (class "Default")
      (node (ref "IC1") (pin "7") (pinfunction "~{QH}_7") (pintype "output+no_connect"))
    )
    (net (code "68") (name "unconnected-(IC2-SERI-Pad10)") (class "Default")
      (node (ref "IC2") (pin "10") (pinfunction "SERI_10") (pintype "input+no_connect"))
    )
    (net (code "69") (name "unconnected-(IC2-~{QH}-Pad7)") (class "Default")
      (node (ref "IC2") (pin "7") (pinfunction "~{QH}_7") (pintype "output+no_connect"))
    )
    (net (code "70") (name "unconnected-(IC3-H-Pad6)") (class "Default")
      (node (ref "IC3") (pin "6") (pinfunction "H_6") (pintype "input+no_connect"))
    )
    (net (code "71") (name "unconnected-(IC3-SERI-Pad10)") (class "Default")
      (node (ref "IC3") (pin "10") (pinfunction "SERI_10") (pintype "input+no_connect"))
    )
    (net (code "72") (name "unconnected-(IC3-~{QH}-Pad7)") (class "Default")
      (node (ref "IC3") (pin "7") (pinfunction "~{QH}_7") (pintype "output+no_connect"))
    )
    (net (code "73") (name "unconnected-(N1-IRQ-Pad8)") (class "Default")
      (node (ref "N1") (pin "8") (pinfunction "IRQ_8") (pintype "passive+no_connect"))
    )
    (net (code "74") (name "unconnected-(U1-3V3-Pad47)") (class "Default")
      (node (ref "U1") (pin "47") (pinfunction "3V3_47") (pintype "passive"))
    )
    (net (code "75") (name "unconnected-(U1-3V3-Pad48)") (class "Default")
      (node (ref "U1") (pin "48") (pinfunction "3V3_48") (pintype "passive"))
    )
    (net (code "76") (name "unconnected-(U1-5V-Pad36)") (class "Default")
      (node (ref "U1") (pin "36") (pinfunction "5V_36") (pintype "passive"))
    )
    (net (code "77") (name "unconnected-(U1-B2-Pad22)") (class "Default")
      (node (ref "U1") (pin "22") (pinfunction "B2_22") (pintype "passive"))
    )
    (net (code "78") (name "unconnected-(U1-GND-Pad35)") (class "Default")
      (node (ref "U1") (pin "35") (pinfunction "GND_35") (pintype "passive"))
    )
    (net (code "79") (name "unconnected-(U1-PB7-Pad43)") (class "Default")
      (node (ref "U1") (pin "43") (pinfunction "PB7_43") (pintype "passive"))
    )
    (net (code "80") (name "unconnected-(U1-PC13-Pad2)") (class "Default")
      (node (ref "U1") (pin "2") (pinfunction "PC13_2") (pintype "passive"))
    )
    (net (code "81") (name "unconnected-(U1-PC14{slash}OSC32_IN-Pad3)") (class "Default")
      (node (ref "U1") (pin "3") (pinfunction "PC14/OSC32_IN_3") (pintype "passive"))
    )
    (net (code "82") (name "unconnected-(U1-PC15{slash}OSC32_OUT-Pad4)") (class "Default")
      (node (ref "U1") (pin "4") (pinfunction "PC15/OSC32_OUT_4") (pintype "passive"))
    )
    (net (code "83") (name "unconnected-(U1-RST-Pad18)") (class "Default")
      (node (ref "U1") (pin "18") (pinfunction "RST_18") (pintype "passive"))
    )
    (net (code "84") (name "unconnected-(U1-VBAT-Pad1)") (class "Default")
      (node (ref "U1") (pin "1") (pinfunction "VBAT_1") (pintype "passive"))
    )
  )
)
